# 18B20.net
KiCad netlist of a schematic drawn in Altium Designer
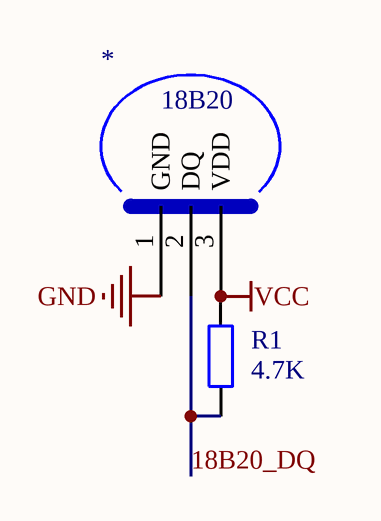
[diagram p0: 18B20.SchDoc]

(export (version "E")
  (design (tool "Eeschema 10.0.6"))
  (components
    (comp (ref "*") (value "18B20") (footprint "HDR1X3") (libsource (lib "原理图库") (part "18B20")))
    (comp (ref "R1")
      (value "4.7K")
      (footprint "AXIAL-0.4")
      (description "Resistor")
      (fields (field (name "Comment") "Res2") (field (name "PUBLISHER") "Altium Limited"))
      (libsource (lib "Miscellaneous Devices") (part "Res2"))
    )
  )
  (nets
    (net (code "1") (name "/18B20_DQ") (class "Default")
      (node (ref "*") (pin "2") (pinfunction "DQ_2") (pintype "passive"))
      (node (ref "R1") (pin "1") (pinfunction "1_1") (pintype "passive"))
    )
    (net (code "2") (name "GND") (class "Default")
      (node (ref "*") (pin "1") (pinfunction "GND_1") (pintype "passive"))
    )
    (net (code "3") (name "VCC") (class "Default")
      (node (ref "*") (pin "3") (pinfunction "VDD_3") (pintype "passive"))
      (node (ref "R1") (pin "2") (pinfunction "2_2") (pintype "passive"))
    )
  )
)
